# Tead_Aliens_64A_Power.net
KiCad netlist of a schematic drawn in Altium Designer
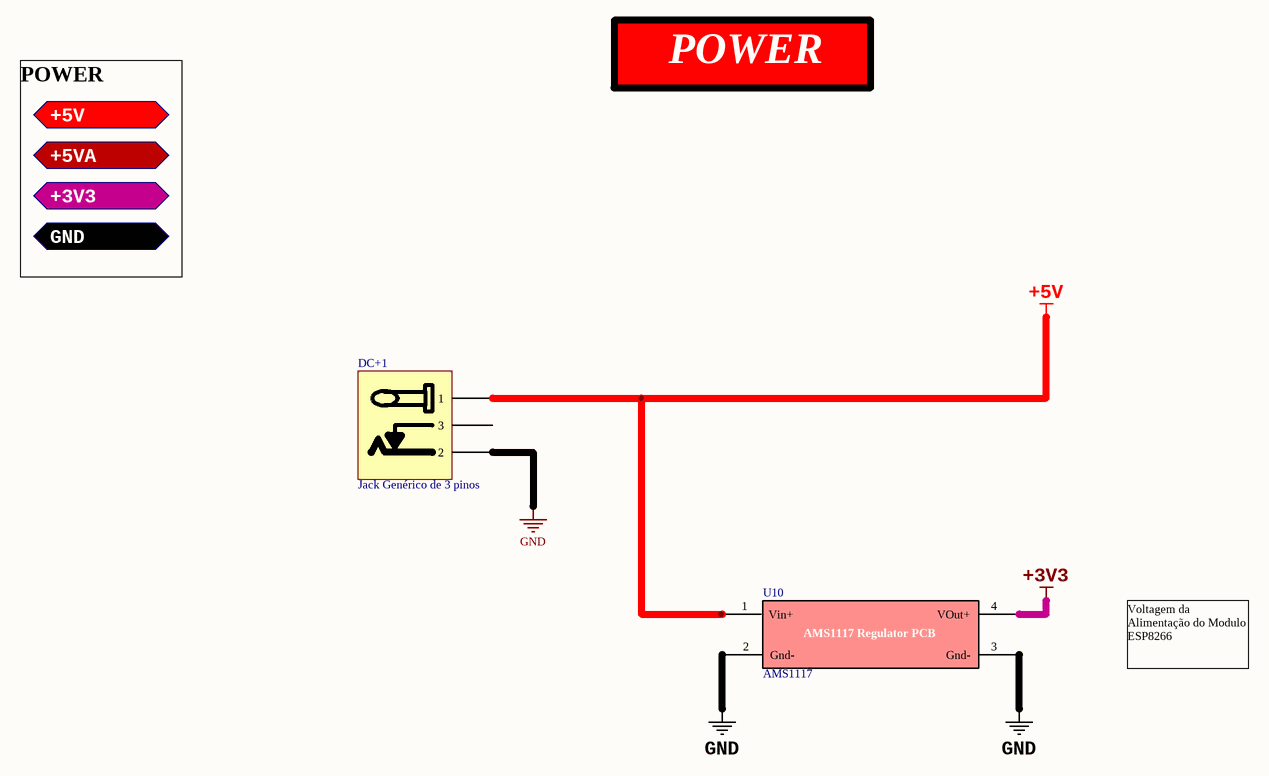
[diagram p0: Tead_Aliens_64A_Power.SchDoc]

(export (version "E")
  (design (tool "Eeschema 10.0.6"))
  (components
    (comp (ref "DC+1")
      (value "Jack Genérico de 3 pinos")
      (footprint "Jack P4")
      (libsource (lib "NEPERMATH") (part "Jack Genérico de 3 pinos"))
    )
    (comp (ref "U10")
      (value "AMS1117")
      (footprint "ANS1117_Reg_Pcb")
      (description "AMS1117 REGULATOR PCB")
      (libsource (lib "NEPERMATH") (part "AMS1117"))
    )
  )
  (nets
    (net (code "1") (name "+3V3") (class "Default")
      (node (ref "U10") (pin "4") (pinfunction "VOut+_4") (pintype "passive"))
    )
    (net (code "2") (name "+5V") (class "Default")
      (node (ref "DC+1") (pin "1") (pinfunction "1_1") (pintype "passive"))
      (node (ref "U10") (pin "1") (pinfunction "Vin+_1") (pintype "passive"))
    )
    (net (code "4") (name "GND") (class "Default")
      (node (ref "DC+1") (pin "2") (pinfunction "2_2") (pintype "passive"))
      (node (ref "U10") (pin "2") (pinfunction "Gnd-_2") (pintype "passive"))
      (node (ref "U10") (pin "3") (pinfunction "Gnd-_3") (pintype "passive"))
    )
    (net (code "5") (name "unconnected-(DC+1-Pad3)") (class "Default")
      (node (ref "DC+1") (pin "3") (pinfunction "3_3") (pintype "passive"))
    )
  )
)
